# EVALUE.net
KiCad netlist of a schematic drawn in Altium Designer
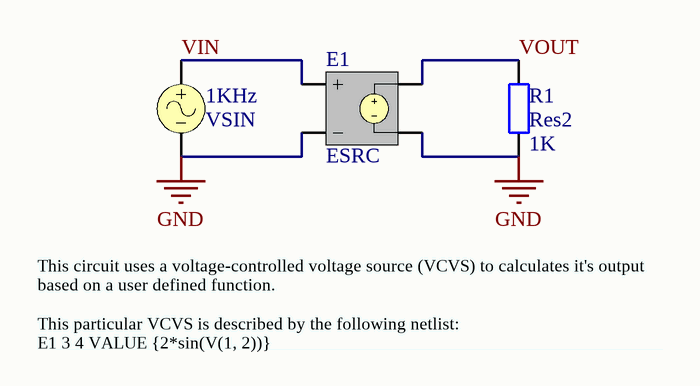
[diagram p0: EVALUE.SchDoc]

(export (version "E")
  (design (tool "Eeschema 10.0.6"))
  (components
    (comp (ref "1KHz")
      (value "VSIN")
      (description "Sinusoidal Voltage Source")
      (fields (field (name "PUBLISHER") "Altium Limited"))
      (libsource (lib "Simulation Sources") (part "VSIN"))
    )
    (comp (ref "E1")
      (value "ESRC")
      (description "Voltage Controlled Voltage Source")
      (fields (field (name "PUBLISHER") "Altium Limited"))
      (libsource (lib "Simulation Sources") (part "ESRC"))
    )
    (comp (ref "R1")
      (value "Res2")
      (footprint "AXIAL-0.4")
      (description "Resistor")
      (fields (field (name "ALTIUM_VALUE") "1K") (field (name "PUBLISHER") "Altium Limited"))
      (libsource (lib "Miscellaneous Devices") (part "Res2"))
    )
  )
  (nets
    (net (code "1") (name "/VIN") (class "Default")
      (node (ref "1KHz") (pin "1") (pinfunction "1_1") (pintype "passive"))
      (node (ref "E1") (pin "1") (pinfunction "NC+_1") (pintype "passive"))
    )
    (net (code "2") (name "/VOUT") (class "Default")
      (node (ref "E1") (pin "3") (pinfunction "N+_3") (pintype "passive"))
      (node (ref "R1") (pin "2") (pinfunction "2_2") (pintype "passive"))
    )
    (net (code "3") (name "GND") (class "Default")
      (node (ref "1KHz") (pin "2") (pinfunction "2_2") (pintype "passive"))
      (node (ref "E1") (pin "2") (pinfunction "NC-_2") (pintype "passive"))
      (node (ref "E1") (pin "4") (pinfunction "N-_4") (pintype "passive"))
      (node (ref "R1") (pin "1") (pinfunction "1_1") (pintype "passive"))
    )
  )
)
